# TinyTX_boost_converter.net
KiCad netlist of a schematic drawn in EAGLE
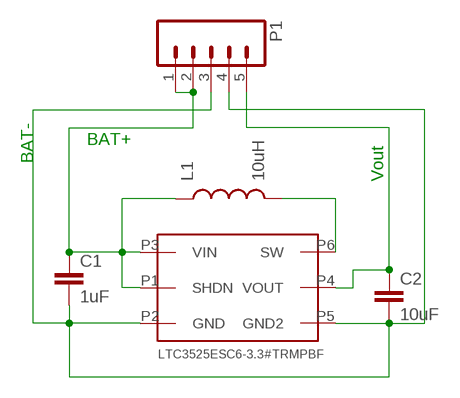
[diagram p0: schematic, sheet 1]

(export (version "E")
  (design (tool "Eeschema 10.0.6"))
  (components
    (comp (ref "C1")
      (value "1uF")
      (footprint "eagle-import:0603-CAP")
      (libsource (lib "eagle-import") (part "1.0UF-16V-10%(0603)"))
    )
    (comp (ref "C2")
      (value "10uF")
      (footprint "eagle-import:0603-CAP")
      (libsource (lib "eagle-import") (part "10UF-6.3V-20%(0603)"))
    )
    (comp (ref "L1")
      (value "10uH")
      (footprint "eagle-import:1210")
      (libsource (lib "eagle-import") (part "INDUCTOR1210"))
    )
    (comp (ref "P1")
      (value "M05PTH")
      (footprint "eagle-import:1X05")
      (libsource (lib "eagle-import") (part "M05PTH"))
    )
    (comp (ref "U1")
      (value "LTC3525")
      (footprint "eagle-import:6-LEAD-SC70")
      (libsource (lib "eagle-import") (part "LTC3525"))
    )
  )
  (nets
    (net (code "1") (name "Net-(U1-GND)") (class "Default")
      (node (ref "C1") (pin "2") (pinfunction "2_2") (pintype "passive"))
      (node (ref "C2") (pin "2") (pinfunction "2_2") (pintype "passive"))
      (node (ref "P1") (pin "3") (pinfunction "3_3") (pintype "passive"))
      (node (ref "P1") (pin "4") (pinfunction "4_4") (pintype "passive"))
      (node (ref "U1") (pin "P2") (pinfunction "GND_P2") (pintype "bidirectional"))
      (node (ref "U1") (pin "P5") (pinfunction "GND2_P5") (pintype "bidirectional"))
    )
    (net (code "2") (name "Net-(U1-SHDN)") (class "Default")
      (node (ref "C1") (pin "1") (pinfunction "1_1") (pintype "passive"))
      (node (ref "L1") (pin "1") (pinfunction "1_1") (pintype "passive"))
      (node (ref "P1") (pin "1") (pinfunction "1_1") (pintype "passive"))
      (node (ref "P1") (pin "2") (pinfunction "2_2") (pintype "passive"))
      (node (ref "U1") (pin "P1") (pinfunction "SHDN_P1") (pintype "bidirectional"))
      (node (ref "U1") (pin "P3") (pinfunction "VIN_P3") (pintype "bidirectional"))
    )
    (net (code "3") (name "Net-(U1-SW)") (class "Default")
      (node (ref "L1") (pin "2") (pinfunction "2_2") (pintype "passive"))
      (node (ref "U1") (pin "P6") (pinfunction "SW_P6") (pintype "bidirectional"))
    )
    (net (code "4") (name "Net-(U1-VOUT)") (class "Default")
      (node (ref "C2") (pin "1") (pinfunction "1_1") (pintype "passive"))
      (node (ref "P1") (pin "5") (pinfunction "5_5") (pintype "passive"))
      (node (ref "U1") (pin "P4") (pinfunction "VOUT_P4") (pintype "bidirectional"))
    )
  )
)
